# Switch_Boosterpack.net
KiCad netlist of a schematic drawn in EAGLE
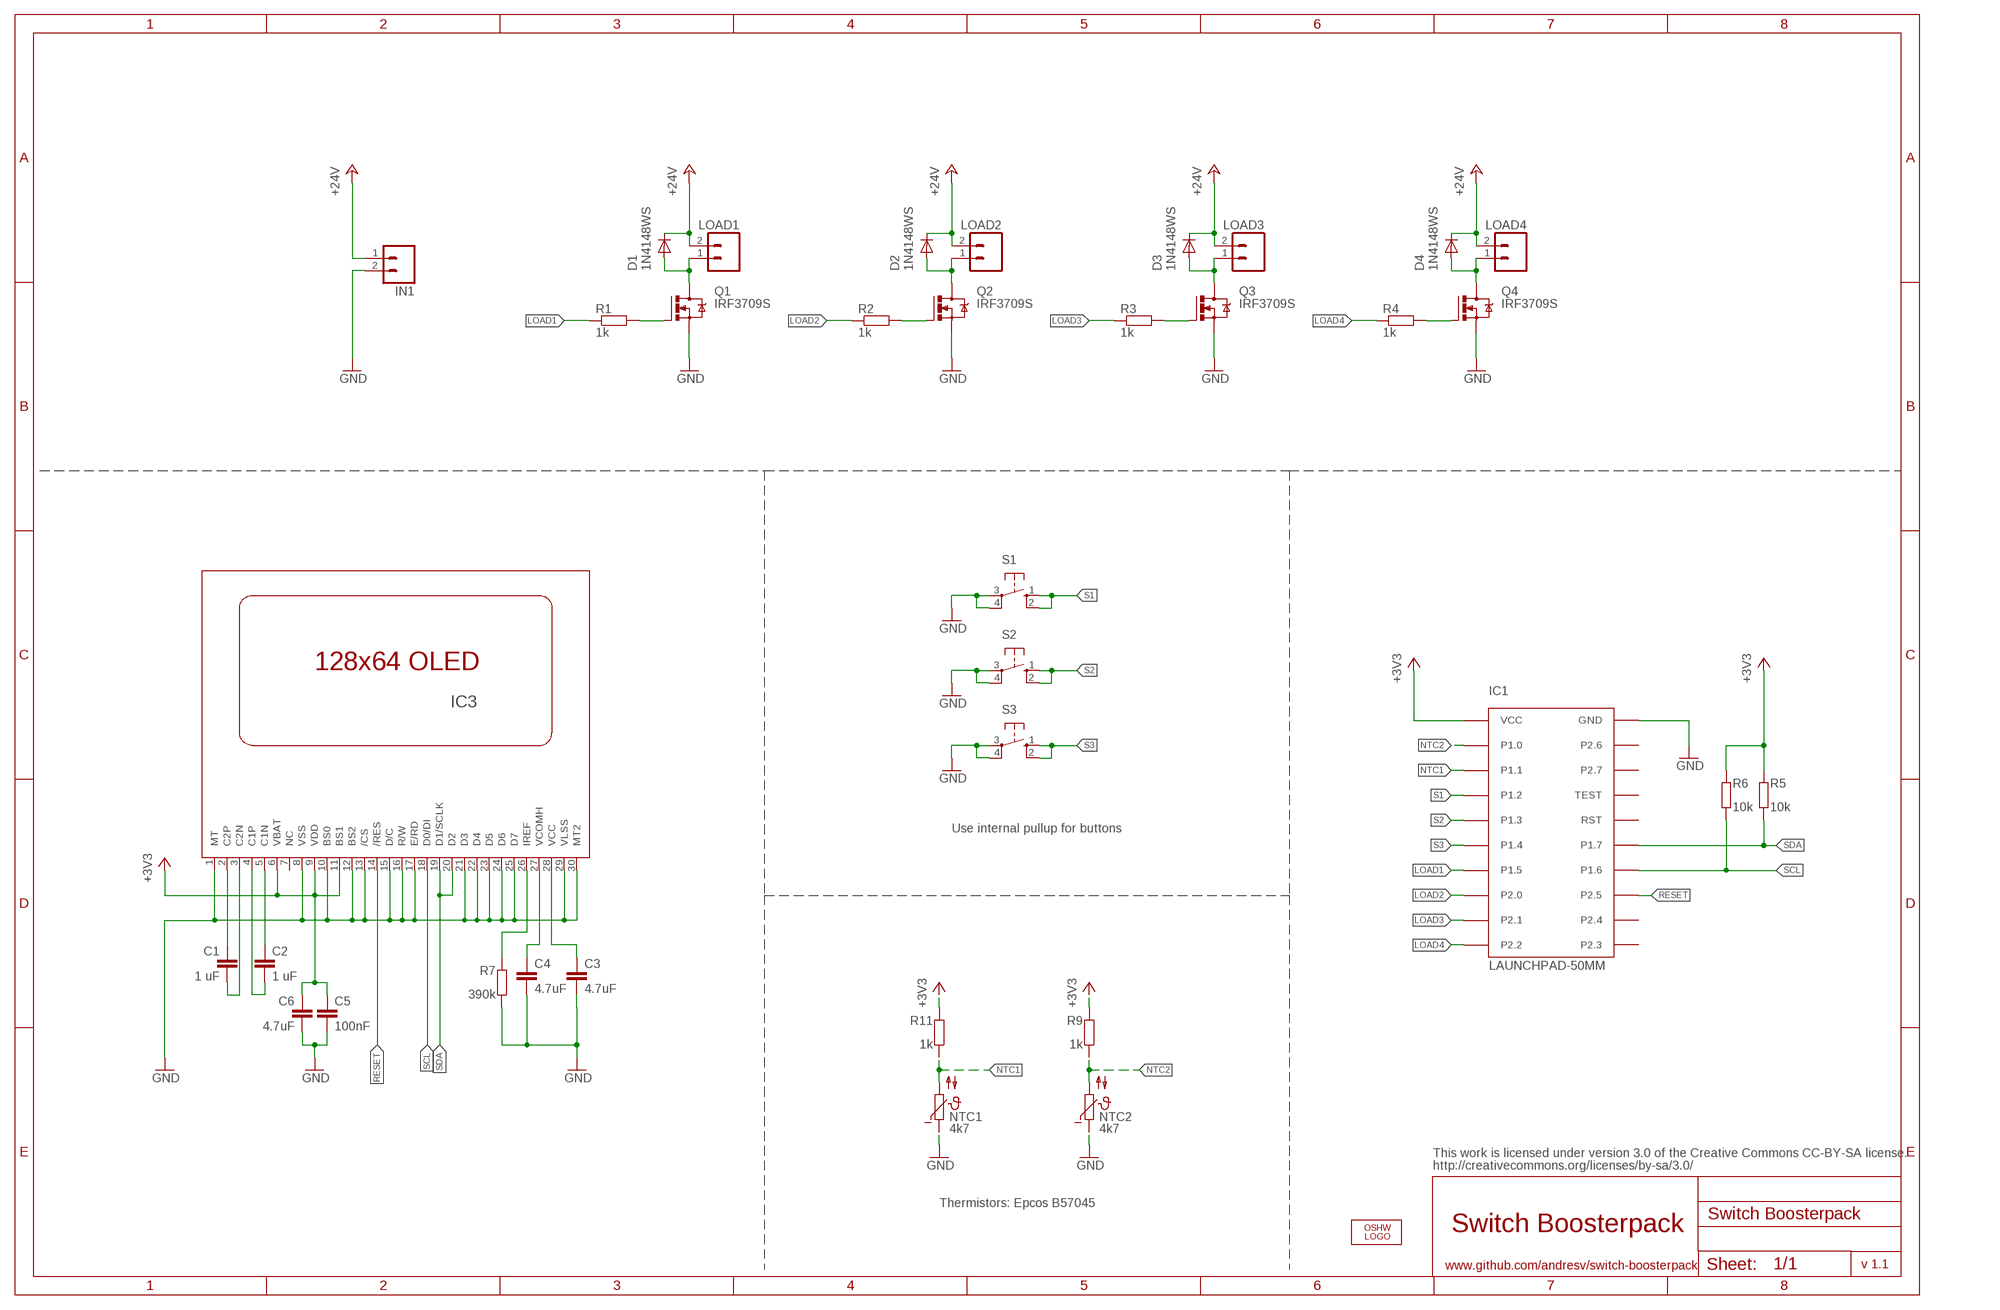
[diagram p0: schematic, sheet 1]

(export (version "E")
  (design (tool "Eeschema 10.0.6"))
  (components
    (comp (ref "C1")
      (value "1 uF")
      (footprint "eagle-import:C0603")
      (libsource (lib "eagle-import") (part "C-EUC0603"))
    )
    (comp (ref "C2")
      (value "1 uF")
      (footprint "eagle-import:C0603")
      (libsource (lib "eagle-import") (part "C-EUC0603"))
    )
    (comp (ref "C3")
      (value "4.7uF")
      (footprint "eagle-import:C0603")
      (libsource (lib "eagle-import") (part "C-EUC0603"))
    )
    (comp (ref "C4")
      (value "4.7uF")
      (footprint "eagle-import:C0603")
      (libsource (lib "eagle-import") (part "C-EUC0603"))
    )
    (comp (ref "C5")
      (value "100nF")
      (footprint "eagle-import:C0603")
      (libsource (lib "eagle-import") (part "C-EUC0603"))
    )
    (comp (ref "C6")
      (value "4.7uF")
      (footprint "eagle-import:C0603")
      (libsource (lib "eagle-import") (part "C-EUC0603"))
    )
    (comp (ref "D1")
      (value "1N4148WS")
      (footprint "eagle-import:SOD323-W")
      (libsource (lib "eagle-import") (part "DIODE-SOD323-W"))
    )
    (comp (ref "D2")
      (value "1N4148WS")
      (footprint "eagle-import:SOD323-W")
      (libsource (lib "eagle-import") (part "DIODE-SOD323-W"))
    )
    (comp (ref "D3")
      (value "1N4148WS")
      (footprint "eagle-import:SOD323-W")
      (libsource (lib "eagle-import") (part "DIODE-SOD323-W"))
    )
    (comp (ref "D4")
      (value "1N4148WS")
      (footprint "eagle-import:SOD323-W")
      (libsource (lib "eagle-import") (part "DIODE-SOD323-W"))
    )
    (comp (ref "IC1")
      (value "LAUNCHPAD-50MM")
      (footprint "eagle-import:LAUNCHPAD-50MM")
      (libsource (lib "eagle-import") (part "LAUNCHPAD-50MM"))
    )
    (comp (ref "IC3")
      (value "UG-2864HSWEG01")
      (footprint "eagle-import:1X30-0.7MM")
      (libsource (lib "eagle-import") (part "UG-2864HSWEG01"))
    )
    (comp (ref "IN1")
      (value "M025MM")
      (footprint "eagle-import:SCREWTERMINAL-5MM-2")
      (libsource (lib "eagle-import") (part "M025MM"))
    )
    (comp (ref "LOAD1")
      (value "M025MM")
      (footprint "eagle-import:SCREWTERMINAL-5MM-2")
      (libsource (lib "eagle-import") (part "M025MM"))
    )
    (comp (ref "LOAD2")
      (value "M025MM")
      (footprint "eagle-import:SCREWTERMINAL-5MM-2")
      (libsource (lib "eagle-import") (part "M025MM"))
    )
    (comp (ref "LOAD3")
      (value "M025MM")
      (footprint "eagle-import:SCREWTERMINAL-5MM-2")
      (libsource (lib "eagle-import") (part "M025MM"))
    )
    (comp (ref "LOAD4")
      (value "M025MM")
      (footprint "eagle-import:SCREWTERMINAL-5MM-2")
      (libsource (lib "eagle-import") (part "M025MM"))
    )
    (comp (ref "LOGO1")
      (value "OSHW_LOGO_8MILX0350-NT")
      (footprint "eagle-import:OSHW_8X350_NOTEXT")
      (libsource (lib "eagle-import") (part "OSHW_LOGO_8MILX0350-NT"))
    )
    (comp (ref "NTC1")
      (value "4k7")
      (footprint "eagle-import:N640")
      (libsource (lib "eagle-import") (part "NTC640-9"))
    )
    (comp (ref "NTC2")
      (value "4k7")
      (footprint "eagle-import:N640")
      (libsource (lib "eagle-import") (part "NTC640-9"))
    )
    (comp (ref "Q1")
      (value "IRF3709S")
      (footprint "eagle-import:D-PAK_TO252AA")
      (libsource (lib "eagle-import") (part "IRFR3709"))
    )
    (comp (ref "Q2")
      (value "IRF3709S")
      (footprint "eagle-import:D-PAK_TO252AA")
      (libsource (lib "eagle-import") (part "IRFR3709"))
    )
    (comp (ref "Q3")
      (value "IRF3709S")
      (footprint "eagle-import:D-PAK_TO252AA")
      (libsource (lib "eagle-import") (part "IRFR3709"))
    )
    (comp (ref "Q4")
      (value "IRF3709S")
      (footprint "eagle-import:D-PAK_TO252AA")
      (libsource (lib "eagle-import") (part "IRFR3709"))
    )
    (comp (ref "R1")
      (value "1k")
      (footprint "eagle-import:R0603")
      (libsource (lib "eagle-import") (part "R-EU_R0603"))
    )
    (comp (ref "R2")
      (value "1k")
      (footprint "eagle-import:R0603")
      (libsource (lib "eagle-import") (part "R-EU_R0603"))
    )
    (comp (ref "R3")
      (value "1k")
      (footprint "eagle-import:R0603")
      (libsource (lib "eagle-import") (part "R-EU_R0603"))
    )
    (comp (ref "R4")
      (value "1k")
      (footprint "eagle-import:R0603")
      (libsource (lib "eagle-import") (part "R-EU_R0603"))
    )
    (comp (ref "R5")
      (value "10k")
      (footprint "eagle-import:R0603")
      (libsource (lib "eagle-import") (part "R-EU_R0603"))
    )
    (comp (ref "R6")
      (value "10k")
      (footprint "eagle-import:R0603")
      (libsource (lib "eagle-import") (part "R-EU_R0603"))
    )
    (comp (ref "R7")
      (value "390k")
      (footprint "eagle-import:R0603")
      (libsource (lib "eagle-import") (part "R-EU_R0603"))
    )
    (comp (ref "R9")
      (value "1k")
      (footprint "eagle-import:R0603")
      (libsource (lib "eagle-import") (part "R-EU_R0603"))
    )
    (comp (ref "R11")
      (value "1k")
      (footprint "eagle-import:R0603")
      (libsource (lib "eagle-import") (part "R-EU_R0603"))
    )
    (comp (ref "S1")
      (value "10-XX")
      (footprint "eagle-import:B3F-10XX")
      (fields (field (name "MPN") "B3F-1000"))
      (libsource (lib "eagle-import") (part "10-XX"))
    )
    (comp (ref "S2")
      (value "10-XX")
      (footprint "eagle-import:B3F-10XX")
      (fields (field (name "MPN") "B3F-1000"))
      (libsource (lib "eagle-import") (part "10-XX"))
    )
    (comp (ref "S3")
      (value "10-XX")
      (footprint "eagle-import:B3F-10XX")
      (fields (field (name "MPN") "B3F-1000"))
      (libsource (lib "eagle-import") (part "10-XX"))
    )
  )
  (nets
    (net (code "1") (name "+3V3") (class "Default")
      (node (ref "C5") (pin "1") (pinfunction "1_1") (pintype "passive"))
      (node (ref "C6") (pin "1") (pinfunction "1_1") (pintype "passive"))
      (node (ref "IC1") (pin "VCC") (pinfunction "VCC_VCC") (pintype "power_in"))
      (node (ref "IC3") (pin "11") (pinfunction "BS1_11") (pintype "input"))
      (node (ref "IC3") (pin "6") (pinfunction "VBAT_6") (pintype "input"))
      (node (ref "IC3") (pin "9") (pinfunction "VDD_9") (pintype "power_in"))
      (node (ref "R11") (pin "2") (pinfunction "2_2") (pintype "passive"))
      (node (ref "R5") (pin "2") (pinfunction "2_2") (pintype "passive"))
      (node (ref "R6") (pin "2") (pinfunction "2_2") (pintype "passive"))
      (node (ref "R9") (pin "2") (pinfunction "2_2") (pintype "passive"))
    )
    (net (code "2") (name "+24V") (class "Default")
      (node (ref "D1") (pin "C") (pinfunction "C_C") (pintype "passive"))
      (node (ref "D2") (pin "C") (pinfunction "C_C") (pintype "passive"))
      (node (ref "D3") (pin "C") (pinfunction "C_C") (pintype "passive"))
      (node (ref "D4") (pin "C") (pinfunction "C_C") (pintype "passive"))
      (node (ref "IN1") (pin "1") (pinfunction "1_1") (pintype "passive"))
      (node (ref "LOAD1") (pin "2") (pinfunction "2_2") (pintype "passive"))
      (node (ref "LOAD2") (pin "2") (pinfunction "2_2") (pintype "passive"))
      (node (ref "LOAD3") (pin "2") (pinfunction "2_2") (pintype "passive"))
      (node (ref "LOAD4") (pin "2") (pinfunction "2_2") (pintype "passive"))
    )
    (net (code "3") (name "GND") (class "Default")
      (node (ref "C3") (pin "2") (pinfunction "2_2") (pintype "passive"))
      (node (ref "C4") (pin "2") (pinfunction "2_2") (pintype "passive"))
      (node (ref "C5") (pin "2") (pinfunction "2_2") (pintype "passive"))
      (node (ref "C6") (pin "2") (pinfunction "2_2") (pintype "passive"))
      (node (ref "IC1") (pin "GND") (pinfunction "GND_GND") (pintype "power_in"))
      (node (ref "IC3") (pin "1") (pinfunction "MT_1") (pintype "input"))
      (node (ref "IC3") (pin "10") (pinfunction "BS0_10") (pintype "input"))
      (node (ref "IC3") (pin "12") (pinfunction "BS2_12") (pintype "input"))
      (node (ref "IC3") (pin "13") (pinfunction "/CS_13") (pintype "input"))
      (node (ref "IC3") (pin "15") (pinfunction "D/C_15") (pintype "input"))
      (node (ref "IC3") (pin "16") (pinfunction "R/W_16") (pintype "input"))
      (node (ref "IC3") (pin "17") (pinfunction "E/RD_17") (pintype "input"))
      (node (ref "IC3") (pin "21") (pinfunction "D3_21") (pintype "bidirectional"))
      (node (ref "IC3") (pin "22") (pinfunction "D4_22") (pintype "bidirectional"))
      (node (ref "IC3") (pin "23") (pinfunction "D5_23") (pintype "bidirectional"))
      (node (ref "IC3") (pin "24") (pinfunction "D6_24") (pintype "bidirectional"))
      (node (ref "IC3") (pin "25") (pinfunction "D7_25") (pintype "bidirectional"))
      (node (ref "IC3") (pin "29") (pinfunction "VLSS_29") (pintype "power_in"))
      (node (ref "IC3") (pin "30") (pinfunction "MT2_30") (pintype "input"))
      (node (ref "IC3") (pin "8") (pinfunction "VSS_8") (pintype "power_in"))
      (node (ref "IN1") (pin "2") (pinfunction "2_2") (pintype "passive"))
      (node (ref "NTC1") (pin "1") (pinfunction "1_1") (pintype "passive"))
      (node (ref "NTC2") (pin "1") (pinfunction "1_1") (pintype "passive"))
      (node (ref "Q1") (pin "3") (pinfunction "S_3") (pintype "passive"))
      (node (ref "Q2") (pin "3") (pinfunction "S_3") (pintype "passive"))
      (node (ref "Q3") (pin "3") (pinfunction "S_3") (pintype "passive"))
      (node (ref "Q4") (pin "3") (pinfunction "S_3") (pintype "passive"))
      (node (ref "R7") (pin "1") (pinfunction "1_1") (pintype "passive"))
      (node (ref "S1") (pin "3") (pinfunction "P_3") (pintype "passive"))
      (node (ref "S1") (pin "4") (pinfunction "P1_4") (pintype "passive"))
      (node (ref "S2") (pin "3") (pinfunction "P_3") (pintype "passive"))
      (node (ref "S2") (pin "4") (pinfunction "P1_4") (pintype "passive"))
      (node (ref "S3") (pin "3") (pinfunction "P_3") (pintype "passive"))
      (node (ref "S3") (pin "4") (pinfunction "P1_4") (pintype "passive"))
    )
    (net (code "4") (name "LOAD1") (class "Default")
      (node (ref "IC1") (pin "P1.5") (pinfunction "P1.5_P1.5") (pintype "bidirectional"))
      (node (ref "R1") (pin "1") (pinfunction "1_1") (pintype "passive"))
    )
    (net (code "5") (name "LOAD2") (class "Default")
      (node (ref "IC1") (pin "P2.0") (pinfunction "P2.0_P2.0") (pintype "bidirectional"))
      (node (ref "R2") (pin "1") (pinfunction "1_1") (pintype "passive"))
    )
    (net (code "6") (name "LOAD3") (class "Default")
      (node (ref "IC1") (pin "P2.1") (pinfunction "P2.1_P2.1") (pintype "bidirectional"))
      (node (ref "R3") (pin "1") (pinfunction "1_1") (pintype "passive"))
    )
    (net (code "7") (name "LOAD4") (class "Default")
      (node (ref "IC1") (pin "P2.2") (pinfunction "P2.2_P2.2") (pintype "bidirectional"))
      (node (ref "R4") (pin "1") (pinfunction "1_1") (pintype "passive"))
    )
    (net (code "8") (name "NTC1") (class "Default")
      (node (ref "IC1") (pin "P1.1") (pinfunction "P1.1_P1.1") (pintype "bidirectional"))
      (node (ref "NTC1") (pin "2") (pinfunction "2_2") (pintype "passive"))
      (node (ref "R11") (pin "1") (pinfunction "1_1") (pintype "passive"))
    )
    (net (code "9") (name "NTC2") (class "Default")
      (node (ref "IC1") (pin "P1.0") (pinfunction "P1.0_P1.0") (pintype "bidirectional"))
      (node (ref "NTC2") (pin "2") (pinfunction "2_2") (pintype "passive"))
      (node (ref "R9") (pin "1") (pinfunction "1_1") (pintype "passive"))
    )
    (net (code "10") (name "Net-(IC3-C1N)") (class "Default")
      (node (ref "C2") (pin "1") (pinfunction "1_1") (pintype "passive"))
      (node (ref "IC3") (pin "5") (pinfunction "C1N_5") (pintype "input"))
    )
    (net (code "11") (name "Net-(IC3-C1P)") (class "Default")
      (node (ref "C2") (pin "2") (pinfunction "2_2") (pintype "passive"))
      (node (ref "IC3") (pin "4") (pinfunction "C1P_4") (pintype "input"))
    )
    (net (code "12") (name "Net-(IC3-C2N)") (class "Default")
      (node (ref "C1") (pin "2") (pinfunction "2_2") (pintype "passive"))
      (node (ref "IC3") (pin "3") (pinfunction "C2N_3") (pintype "input"))
    )
    (net (code "13") (name "Net-(IC3-C2P)") (class "Default")
      (node (ref "C1") (pin "1") (pinfunction "1_1") (pintype "passive"))
      (node (ref "IC3") (pin "2") (pinfunction "C2P_2") (pintype "input"))
    )
    (net (code "14") (name "Net-(IC3-IREF)") (class "Default")
      (node (ref "IC3") (pin "26") (pinfunction "IREF_26") (pintype "input"))
      (node (ref "R7") (pin "2") (pinfunction "2_2") (pintype "passive"))
    )
    (net (code "15") (name "Net-(IC3-VCC)") (class "Default")
      (node (ref "C3") (pin "1") (pinfunction "1_1") (pintype "passive"))
      (node (ref "IC3") (pin "28") (pinfunction "VCC_28") (pintype "power_in"))
    )
    (net (code "16") (name "Net-(IC3-VCOMH)") (class "Default")
      (node (ref "C4") (pin "1") (pinfunction "1_1") (pintype "passive"))
      (node (ref "IC3") (pin "27") (pinfunction "VCOMH_27") (pintype "output"))
    )
    (net (code "17") (name "Net-(Q1-D)") (class "Default")
      (node (ref "D1") (pin "A") (pinfunction "A_A") (pintype "passive"))
      (node (ref "LOAD1") (pin "1") (pinfunction "1_1") (pintype "passive"))
      (node (ref "Q1") (pin "4") (pinfunction "D_4") (pintype "passive"))
    )
    (net (code "18") (name "Net-(Q1-G)") (class "Default")
      (node (ref "Q1") (pin "1") (pinfunction "G_1") (pintype "passive"))
      (node (ref "R1") (pin "2") (pinfunction "2_2") (pintype "passive"))
    )
    (net (code "19") (name "Net-(Q2-D)") (class "Default")
      (node (ref "D2") (pin "A") (pinfunction "A_A") (pintype "passive"))
      (node (ref "LOAD2") (pin "1") (pinfunction "1_1") (pintype "passive"))
      (node (ref "Q2") (pin "4") (pinfunction "D_4") (pintype "passive"))
    )
    (net (code "20") (name "Net-(Q2-G)") (class "Default")
      (node (ref "Q2") (pin "1") (pinfunction "G_1") (pintype "passive"))
      (node (ref "R2") (pin "2") (pinfunction "2_2") (pintype "passive"))
    )
    (net (code "21") (name "Net-(Q3-D)") (class "Default")
      (node (ref "D3") (pin "A") (pinfunction "A_A") (pintype "passive"))
      (node (ref "LOAD3") (pin "1") (pinfunction "1_1") (pintype "passive"))
      (node (ref "Q3") (pin "4") (pinfunction "D_4") (pintype "passive"))
    )
    (net (code "22") (name "Net-(Q3-G)") (class "Default")
      (node (ref "Q3") (pin "1") (pinfunction "G_1") (pintype "passive"))
      (node (ref "R3") (pin "2") (pinfunction "2_2") (pintype "passive"))
    )
    (net (code "23") (name "Net-(Q4-D)") (class "Default")
      (node (ref "D4") (pin "A") (pinfunction "A_A") (pintype "passive"))
      (node (ref "LOAD4") (pin "1") (pinfunction "1_1") (pintype "passive"))
      (node (ref "Q4") (pin "4") (pinfunction "D_4") (pintype "passive"))
    )
    (net (code "24") (name "Net-(Q4-G)") (class "Default")
      (node (ref "Q4") (pin "1") (pinfunction "G_1") (pintype "passive"))
      (node (ref "R4") (pin "2") (pinfunction "2_2") (pintype "passive"))
    )
    (net (code "25") (name "RESET") (class "Default")
      (node (ref "IC1") (pin "P2.5") (pinfunction "P2.5_P2.5") (pintype "bidirectional"))
      (node (ref "IC3") (pin "14") (pinfunction "/RES_14") (pintype "input"))
    )
    (net (code "26") (name "S1") (class "Default")
      (node (ref "IC1") (pin "P1.2") (pinfunction "P1.2_P1.2") (pintype "bidirectional"))
      (node (ref "S1") (pin "1") (pinfunction "S_1") (pintype "passive"))
      (node (ref "S1") (pin "2") (pinfunction "S1_2") (pintype "passive"))
    )
    (net (code "27") (name "S2") (class "Default")
      (node (ref "IC1") (pin "P1.3") (pinfunction "P1.3_P1.3") (pintype "bidirectional"))
      (node (ref "S2") (pin "1") (pinfunction "S_1") (pintype "passive"))
      (node (ref "S2") (pin "2") (pinfunction "S1_2") (pintype "passive"))
    )
    (net (code "28") (name "S3") (class "Default")
      (node (ref "IC1") (pin "P1.4") (pinfunction "P1.4_P1.4") (pintype "bidirectional"))
      (node (ref "S3") (pin "1") (pinfunction "S_1") (pintype "passive"))
      (node (ref "S3") (pin "2") (pinfunction "S1_2") (pintype "passive"))
    )
    (net (code "29") (name "SCL") (class "Default")
      (node (ref "IC1") (pin "P1.6") (pinfunction "P1.6_P1.6") (pintype "bidirectional"))
      (node (ref "IC3") (pin "18") (pinfunction "D0/DI_18") (pintype "bidirectional"))
      (node (ref "R6") (pin "1") (pinfunction "1_1") (pintype "passive"))
    )
    (net (code "30") (name "SDA") (class "Default")
      (node (ref "IC1") (pin "P1.7") (pinfunction "P1.7_P1.7") (pintype "bidirectional"))
      (node (ref "IC3") (pin "19") (pinfunction "D1/SCLK_19") (pintype "bidirectional"))
      (node (ref "IC3") (pin "20") (pinfunction "D2_20") (pintype "bidirectional"))
      (node (ref "R5") (pin "1") (pinfunction "1_1") (pintype "passive"))
    )
    (net (code "31") (name "unconnected-(IC1-PadP2.3)") (class "Default")
      (node (ref "IC1") (pin "P2.3") (pinfunction "P2.3_P2.3") (pintype "bidirectional"))
    )
    (net (code "32") (name "unconnected-(IC1-PadP2.4)") (class "Default")
      (node (ref "IC1") (pin "P2.4") (pinfunction "P2.4_P2.4") (pintype "bidirectional"))
    )
    (net (code "33") (name "unconnected-(IC1-PadP2.6)") (class "Default")
      (node (ref "IC1") (pin "P2.6") (pinfunction "P2.6_P2.6") (pintype "bidirectional"))
    )
    (net (code "34") (name "unconnected-(IC1-PadP2.7)") (class "Default")
      (node (ref "IC1") (pin "P2.7") (pinfunction "P2.7_P2.7") (pintype "bidirectional"))
    )
    (net (code "35") (name "unconnected-(IC1-PadRST)") (class "Default")
      (node (ref "IC1") (pin "RST") (pinfunction "RST_RST") (pintype "bidirectional"))
    )
    (net (code "36") (name "unconnected-(IC1-PadTEST)") (class "Default")
      (node (ref "IC1") (pin "TEST") (pinfunction "TEST_TEST") (pintype "bidirectional"))
    )
    (net (code "37") (name "unconnected-(IC3-NC-Pad7)") (class "Default")
      (node (ref "IC3") (pin "7") (pinfunction "NC_7") (pintype "no_connect"))
    )
  )
)
